# octosonarX2.net
KiCad netlist of a schematic drawn in EAGLE
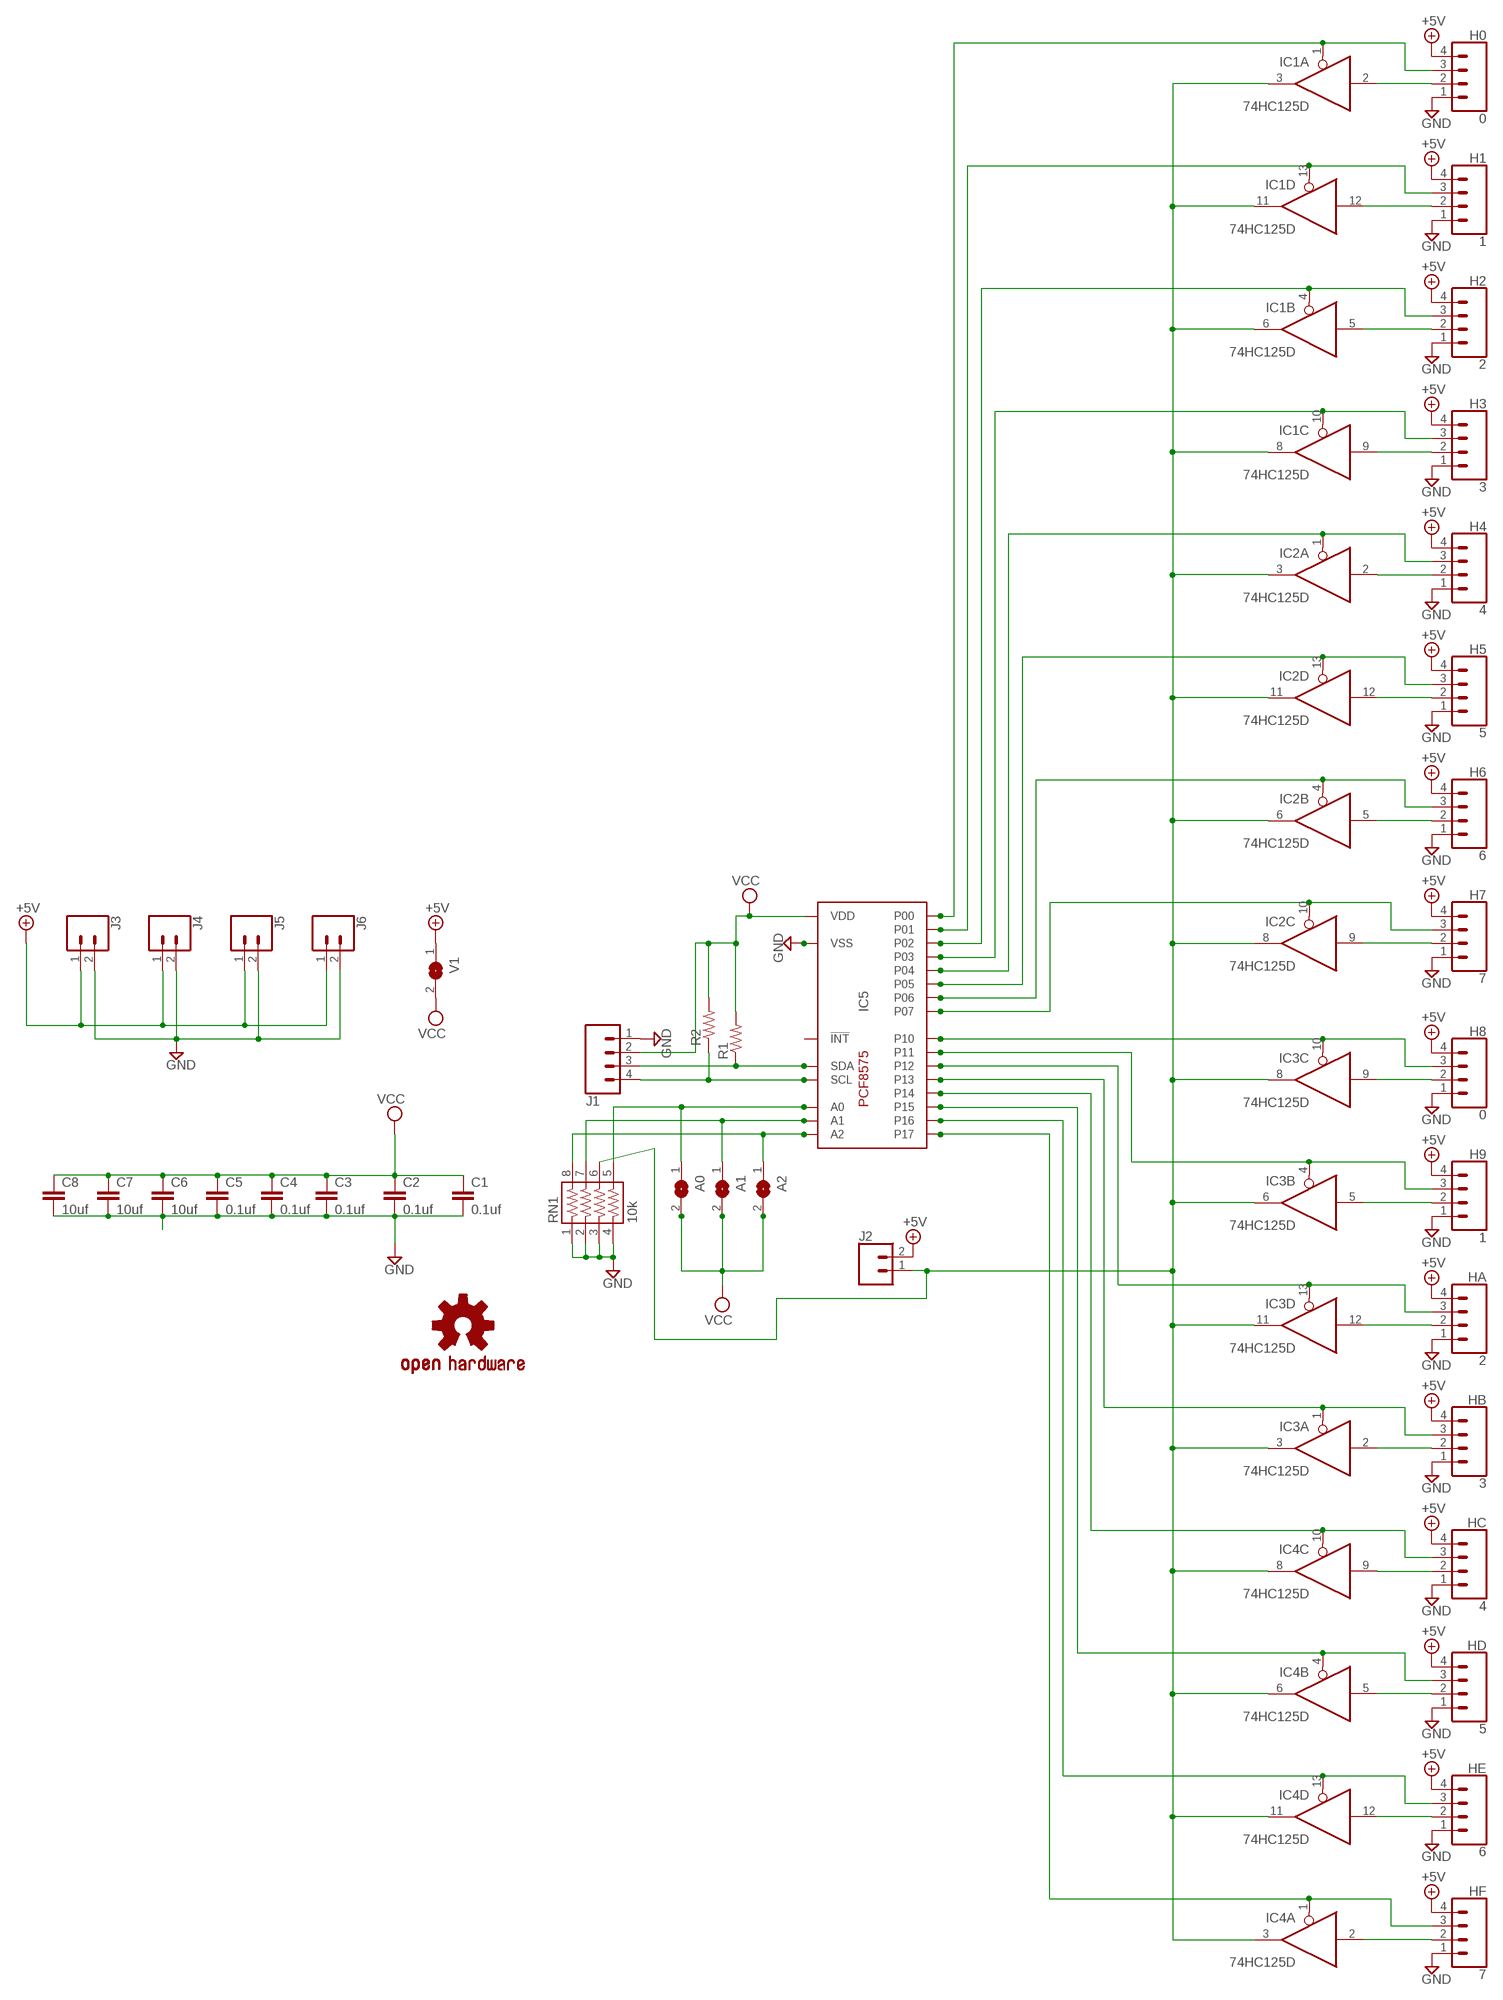
[diagram p0: schematic, sheet 1]

(export (version "E")
  (design (tool "Eeschema 10.0.6"))
  (components
    (comp (ref "A0") (value "SJ") (footprint "eagle-import:SJ") (libsource (lib "eagle-import") (part "SJ")))
    (comp (ref "A1") (value "SJ") (footprint "eagle-import:SJ") (libsource (lib "eagle-import") (part "SJ")))
    (comp (ref "A2") (value "SJ") (footprint "eagle-import:SJ") (libsource (lib "eagle-import") (part "SJ")))
    (comp (ref "C1")
      (value "0.1uf")
      (footprint "eagle-import:C0603")
      (libsource (lib "eagle-import") (part "C-EUC0603"))
    )
    (comp (ref "C2")
      (value "0.1uf")
      (footprint "eagle-import:C0603")
      (libsource (lib "eagle-import") (part "C-EUC0603"))
    )
    (comp (ref "C3")
      (value "0.1uf")
      (footprint "eagle-import:C0603")
      (libsource (lib "eagle-import") (part "C-EUC0603"))
    )
    (comp (ref "C4")
      (value "0.1uf")
      (footprint "eagle-import:C0603")
      (libsource (lib "eagle-import") (part "C-EUC0603"))
    )
    (comp (ref "C5")
      (value "0.1uf")
      (footprint "eagle-import:C0603")
      (libsource (lib "eagle-import") (part "C-EUC0603"))
    )
    (comp (ref "C6")
      (value "10uf")
      (footprint "eagle-import:C0603")
      (libsource (lib "eagle-import") (part "C-EUC0603"))
    )
    (comp (ref "C7")
      (value "10uf")
      (footprint "eagle-import:C0805")
      (libsource (lib "eagle-import") (part "C-EUC0805"))
    )
    (comp (ref "C8")
      (value "10uf")
      (footprint "eagle-import:C0805")
      (libsource (lib "eagle-import") (part "C-EUC0805"))
    )
    (comp (ref "H0")
      (value "0")
      (footprint "eagle-import:1X04")
      (libsource (lib "eagle-import") (part "CONN_04"))
    )
    (comp (ref "H1")
      (value "1")
      (footprint "eagle-import:1X04")
      (libsource (lib "eagle-import") (part "CONN_04"))
    )
    (comp (ref "H2")
      (value "2")
      (footprint "eagle-import:1X04")
      (libsource (lib "eagle-import") (part "CONN_04"))
    )
    (comp (ref "H3")
      (value "3")
      (footprint "eagle-import:1X04")
      (libsource (lib "eagle-import") (part "CONN_04"))
    )
    (comp (ref "H4")
      (value "4")
      (footprint "eagle-import:1X04")
      (libsource (lib "eagle-import") (part "CONN_04"))
    )
    (comp (ref "H5")
      (value "5")
      (footprint "eagle-import:1X04")
      (libsource (lib "eagle-import") (part "CONN_04"))
    )
    (comp (ref "H6")
      (value "6")
      (footprint "eagle-import:1X04")
      (libsource (lib "eagle-import") (part "CONN_04"))
    )
    (comp (ref "H7")
      (value "7")
      (footprint "eagle-import:1X04")
      (libsource (lib "eagle-import") (part "CONN_04"))
    )
    (comp (ref "H8")
      (value "0")
      (footprint "eagle-import:1X04")
      (libsource (lib "eagle-import") (part "CONN_04"))
    )
    (comp (ref "H9")
      (value "1")
      (footprint "eagle-import:1X04")
      (libsource (lib "eagle-import") (part "CONN_04"))
    )
    (comp (ref "HA")
      (value "2")
      (footprint "eagle-import:1X04")
      (libsource (lib "eagle-import") (part "CONN_04"))
    )
    (comp (ref "HB")
      (value "3")
      (footprint "eagle-import:1X04")
      (libsource (lib "eagle-import") (part "CONN_04"))
    )
    (comp (ref "HC")
      (value "4")
      (footprint "eagle-import:1X04")
      (libsource (lib "eagle-import") (part "CONN_04"))
    )
    (comp (ref "HD")
      (value "5")
      (footprint "eagle-import:1X04")
      (libsource (lib "eagle-import") (part "CONN_04"))
    )
    (comp (ref "HE")
      (value "6")
      (footprint "eagle-import:1X04")
      (libsource (lib "eagle-import") (part "CONN_04"))
    )
    (comp (ref "HF")
      (value "7")
      (footprint "eagle-import:1X04")
      (libsource (lib "eagle-import") (part "CONN_04"))
    )
    (comp (ref "IC1")
      (value "74HC125D")
      (footprint "eagle-import:SO14")
      (libsource (lib "eagle-import") (part "74125DHC"))
    )
    (comp (ref "IC2")
      (value "74HC125D")
      (footprint "eagle-import:SO14")
      (libsource (lib "eagle-import") (part "74125DHC"))
    )
    (comp (ref "IC3")
      (value "74HC125D")
      (footprint "eagle-import:SO14")
      (libsource (lib "eagle-import") (part "74xx-eu_85_74125DHC"))
    )
    (comp (ref "IC4")
      (value "74HC125D")
      (footprint "eagle-import:SO14")
      (libsource (lib "eagle-import") (part "74xx-eu_85_74125DHC"))
    )
    (comp (ref "IC5")
      (value "PCF8575C")
      (footprint "eagle-import:SOP24")
      (libsource (lib "eagle-import") (part "PCF8575C"))
    )
    (comp (ref "J1")
      (value "CONN_04POLAR_LOCK")
      (footprint "eagle-import:MOLEX-1X4_LOCK")
      (libsource (lib "eagle-import") (part "CONN_04POLAR_LOCK"))
    )
    (comp (ref "J2")
      (value "CONN_02POLAR_LOCK")
      (footprint "eagle-import:MOLEX-1X2_LOCK")
      (libsource (lib "eagle-import") (part "CONN_02POLAR_LOCK"))
    )
    (comp (ref "J3")
      (value "CONN_02")
      (footprint "eagle-import:1X02")
      (libsource (lib "eagle-import") (part "CONN_02"))
    )
    (comp (ref "J4")
      (value "CONN_02")
      (footprint "eagle-import:1X02")
      (libsource (lib "eagle-import") (part "CONN_02"))
    )
    (comp (ref "J5")
      (value "CONN_02")
      (footprint "eagle-import:1X02")
      (libsource (lib "eagle-import") (part "CONN_02"))
    )
    (comp (ref "J6")
      (value "CONN_02")
      (footprint "eagle-import:1X02")
      (libsource (lib "eagle-import") (part "CONN_02"))
    )
    (comp (ref "LOGO1")
      (value "OSHW-LOGOL")
      (footprint "eagle-import:OSHW-LOGO-L")
      (libsource (lib "eagle-import") (part "OSHW-LOGOL"))
    )
    (comp (ref "R1")
      (value "R-US_0204/2V")
      (footprint "eagle-import:0204V")
      (libsource (lib "eagle-import") (part "R-US_0204/2V"))
    )
    (comp (ref "R2")
      (value "R-US_0204/2V")
      (footprint "eagle-import:0204V")
      (libsource (lib "eagle-import") (part "R-US_0204/2V"))
    )
    (comp (ref "RN1")
      (value "10k")
      (footprint "eagle-import:743-8")
      (libsource (lib "eagle-import") (part "743-8"))
    )
    (comp (ref "V1") (value "SJ") (footprint "eagle-import:SJ") (libsource (lib "eagle-import") (part "SJ")))
  )
  (nets
    (net (code "1") (name "+5V") (class "Default")
      (node (ref "H0") (pin "4") (pinfunction "4_4") (pintype "passive"))
      (node (ref "H1") (pin "4") (pinfunction "4_4") (pintype "passive"))
      (node (ref "H2") (pin "4") (pinfunction "4_4") (pintype "passive"))
      (node (ref "H3") (pin "4") (pinfunction "4_4") (pintype "passive"))
      (node (ref "H4") (pin "4") (pinfunction "4_4") (pintype "passive"))
      (node (ref "H5") (pin "4") (pinfunction "4_4") (pintype "passive"))
      (node (ref "H6") (pin "4") (pinfunction "4_4") (pintype "passive"))
      (node (ref "H7") (pin "4") (pinfunction "4_4") (pintype "passive"))
      (node (ref "H8") (pin "4") (pinfunction "4_4") (pintype "passive"))
      (node (ref "H9") (pin "4") (pinfunction "4_4") (pintype "passive"))
      (node (ref "HA") (pin "4") (pinfunction "4_4") (pintype "passive"))
      (node (ref "HB") (pin "4") (pinfunction "4_4") (pintype "passive"))
      (node (ref "HC") (pin "4") (pinfunction "4_4") (pintype "passive"))
      (node (ref "HD") (pin "4") (pinfunction "4_4") (pintype "passive"))
      (node (ref "HE") (pin "4") (pinfunction "4_4") (pintype "passive"))
      (node (ref "HF") (pin "4") (pinfunction "4_4") (pintype "passive"))
      (node (ref "J2") (pin "2") (pinfunction "2_2") (pintype "passive"))
      (node (ref "J3") (pin "1") (pinfunction "1_1") (pintype "passive"))
      (node (ref "J4") (pin "1") (pinfunction "1_1") (pintype "passive"))
      (node (ref "J5") (pin "1") (pinfunction "1_1") (pintype "passive"))
      (node (ref "J6") (pin "1") (pinfunction "1_1") (pintype "passive"))
      (node (ref "V1") (pin "1") (pinfunction "1_1") (pintype "passive"))
    )
    (net (code "2") (name "GND") (class "Default")
      (node (ref "C1") (pin "2") (pinfunction "2_2") (pintype "passive"))
      (node (ref "C2") (pin "2") (pinfunction "2_2") (pintype "passive"))
      (node (ref "C3") (pin "2") (pinfunction "2_2") (pintype "passive"))
      (node (ref "C4") (pin "2") (pinfunction "2_2") (pintype "passive"))
      (node (ref "C5") (pin "2") (pinfunction "2_2") (pintype "passive"))
      (node (ref "C6") (pin "2") (pinfunction "2_2") (pintype "passive"))
      (node (ref "C7") (pin "2") (pinfunction "2_2") (pintype "passive"))
      (node (ref "C8") (pin "2") (pinfunction "2_2") (pintype "passive"))
      (node (ref "H0") (pin "1") (pinfunction "1_1") (pintype "passive"))
      (node (ref "H1") (pin "1") (pinfunction "1_1") (pintype "passive"))
      (node (ref "H2") (pin "1") (pinfunction "1_1") (pintype "passive"))
      (node (ref "H3") (pin "1") (pinfunction "1_1") (pintype "passive"))
      (node (ref "H4") (pin "1") (pinfunction "1_1") (pintype "passive"))
      (node (ref "H5") (pin "1") (pinfunction "1_1") (pintype "passive"))
      (node (ref "H6") (pin "1") (pinfunction "1_1") (pintype "passive"))
      (node (ref "H7") (pin "1") (pinfunction "1_1") (pintype "passive"))
      (node (ref "H8") (pin "1") (pinfunction "1_1") (pintype "passive"))
      (node (ref "H9") (pin "1") (pinfunction "1_1") (pintype "passive"))
      (node (ref "HA") (pin "1") (pinfunction "1_1") (pintype "passive"))
      (node (ref "HB") (pin "1") (pinfunction "1_1") (pintype "passive"))
      (node (ref "HC") (pin "1") (pinfunction "1_1") (pintype "passive"))
      (node (ref "HD") (pin "1") (pinfunction "1_1") (pintype "passive"))
      (node (ref "HE") (pin "1") (pinfunction "1_1") (pintype "passive"))
      (node (ref "HF") (pin "1") (pinfunction "1_1") (pintype "passive"))
      (node (ref "IC5") (pin "P$12") (pinfunction "VSS_P$12") (pintype "power_in"))
      (node (ref "J1") (pin "1") (pinfunction "1_1") (pintype "passive"))
      (node (ref "J3") (pin "2") (pinfunction "2_2") (pintype "passive"))
      (node (ref "J4") (pin "2") (pinfunction "2_2") (pintype "passive"))
      (node (ref "J5") (pin "2") (pinfunction "2_2") (pintype "passive"))
      (node (ref "J6") (pin "2") (pinfunction "2_2") (pintype "passive"))
      (node (ref "RN1") (pin "1") (pinfunction "1_1") (pintype "passive"))
      (node (ref "RN1") (pin "2") (pinfunction "2_2") (pintype "passive"))
      (node (ref "RN1") (pin "3") (pinfunction "3_3") (pintype "passive"))
      (node (ref "RN1") (pin "4") (pinfunction "4_4") (pintype "passive"))
    )
    (net (code "3") (name "Net-(IC1A-I)") (class "Default")
      (node (ref "H0") (pin "2") (pinfunction "2_2") (pintype "passive"))
      (node (ref "IC1") (pin "2") (pinfunction "I_2") (pintype "input"))
    )
    (net (code "4") (name "Net-(IC1A-O)") (class "Default")
      (node (ref "IC1") (pin "11") (pinfunction "O_11") (pintype "tri_state"))
      (node (ref "IC1") (pin "3") (pinfunction "O_3") (pintype "tri_state"))
      (node (ref "IC1") (pin "6") (pinfunction "O_6") (pintype "tri_state"))
      (node (ref "IC1") (pin "8") (pinfunction "O_8") (pintype "tri_state"))
      (node (ref "IC2") (pin "11") (pinfunction "O_11") (pintype "tri_state"))
      (node (ref "IC2") (pin "3") (pinfunction "O_3") (pintype "tri_state"))
      (node (ref "IC2") (pin "6") (pinfunction "O_6") (pintype "tri_state"))
      (node (ref "IC2") (pin "8") (pinfunction "O_8") (pintype "tri_state"))
      (node (ref "IC3") (pin "11") (pinfunction "O_11") (pintype "tri_state"))
      (node (ref "IC3") (pin "3") (pinfunction "O_3") (pintype "tri_state"))
      (node (ref "IC3") (pin "6") (pinfunction "O_6") (pintype "tri_state"))
      (node (ref "IC3") (pin "8") (pinfunction "O_8") (pintype "tri_state"))
      (node (ref "IC4") (pin "11") (pinfunction "O_11") (pintype "tri_state"))
      (node (ref "IC4") (pin "3") (pinfunction "O_3") (pintype "tri_state"))
      (node (ref "IC4") (pin "6") (pinfunction "O_6") (pintype "tri_state"))
      (node (ref "IC4") (pin "8") (pinfunction "O_8") (pintype "tri_state"))
      (node (ref "J2") (pin "1") (pinfunction "1_1") (pintype "passive"))
      (node (ref "RN1") (pin "6") (pinfunction "6_6") (pintype "passive"))
    )
    (net (code "5") (name "Net-(IC1A-OE)") (class "Default")
      (node (ref "H0") (pin "3") (pinfunction "3_3") (pintype "passive"))
      (node (ref "IC1") (pin "1") (pinfunction "OE_1") (pintype "input"))
      (node (ref "IC5") (pin "P$4") (pinfunction "P00_P$4") (pintype "bidirectional"))
    )
    (net (code "6") (name "Net-(IC1B-I)") (class "Default")
      (node (ref "H2") (pin "2") (pinfunction "2_2") (pintype "passive"))
      (node (ref "IC1") (pin "5") (pinfunction "I_5") (pintype "input"))
    )
    (net (code "7") (name "Net-(IC1B-OE)") (class "Default")
      (node (ref "H2") (pin "3") (pinfunction "3_3") (pintype "passive"))
      (node (ref "IC1") (pin "4") (pinfunction "OE_4") (pintype "input"))
      (node (ref "IC5") (pin "P$6") (pinfunction "P02_P$6") (pintype "bidirectional"))
    )
    (net (code "8") (name "Net-(IC1C-I)") (class "Default")
      (node (ref "H3") (pin "2") (pinfunction "2_2") (pintype "passive"))
      (node (ref "IC1") (pin "9") (pinfunction "I_9") (pintype "input"))
    )
    (net (code "9") (name "Net-(IC1C-OE)") (class "Default")
      (node (ref "H3") (pin "3") (pinfunction "3_3") (pintype "passive"))
      (node (ref "IC1") (pin "10") (pinfunction "OE_10") (pintype "input"))
      (node (ref "IC5") (pin "P$7") (pinfunction "P03_P$7") (pintype "bidirectional"))
    )
    (net (code "10") (name "Net-(IC1D-I)") (class "Default")
      (node (ref "H1") (pin "2") (pinfunction "2_2") (pintype "passive"))
      (node (ref "IC1") (pin "12") (pinfunction "I_12") (pintype "input"))
    )
    (net (code "11") (name "Net-(IC1D-OE)") (class "Default")
      (node (ref "H1") (pin "3") (pinfunction "3_3") (pintype "passive"))
      (node (ref "IC1") (pin "13") (pinfunction "OE_13") (pintype "input"))
      (node (ref "IC5") (pin "P$5") (pinfunction "P01_P$5") (pintype "bidirectional"))
    )
    (net (code "12") (name "Net-(IC2A-I)") (class "Default")
      (node (ref "H4") (pin "2") (pinfunction "2_2") (pintype "passive"))
      (node (ref "IC2") (pin "2") (pinfunction "I_2") (pintype "input"))
    )
    (net (code "13") (name "Net-(IC2A-OE)") (class "Default")
      (node (ref "H4") (pin "3") (pinfunction "3_3") (pintype "passive"))
      (node (ref "IC2") (pin "1") (pinfunction "OE_1") (pintype "input"))
      (node (ref "IC5") (pin "P$8") (pinfunction "P04_P$8") (pintype "bidirectional"))
    )
    (net (code "14") (name "Net-(IC2B-I)") (class "Default")
      (node (ref "H6") (pin "2") (pinfunction "2_2") (pintype "passive"))
      (node (ref "IC2") (pin "5") (pinfunction "I_5") (pintype "input"))
    )
    (net (code "15") (name "Net-(IC2B-OE)") (class "Default")
      (node (ref "H6") (pin "3") (pinfunction "3_3") (pintype "passive"))
      (node (ref "IC2") (pin "4") (pinfunction "OE_4") (pintype "input"))
      (node (ref "IC5") (pin "P$10") (pinfunction "P06_P$10") (pintype "bidirectional"))
    )
    (net (code "16") (name "Net-(IC2C-I)") (class "Default")
      (node (ref "H7") (pin "2") (pinfunction "2_2") (pintype "passive"))
      (node (ref "IC2") (pin "9") (pinfunction "I_9") (pintype "input"))
    )
    (net (code "17") (name "Net-(IC2C-OE)") (class "Default")
      (node (ref "H7") (pin "3") (pinfunction "3_3") (pintype "passive"))
      (node (ref "IC2") (pin "10") (pinfunction "OE_10") (pintype "input"))
      (node (ref "IC5") (pin "P$11") (pinfunction "P07_P$11") (pintype "bidirectional"))
    )
    (net (code "18") (name "Net-(IC2D-I)") (class "Default")
      (node (ref "H5") (pin "2") (pinfunction "2_2") (pintype "passive"))
      (node (ref "IC2") (pin "12") (pinfunction "I_12") (pintype "input"))
    )
    (net (code "19") (name "Net-(IC2D-OE)") (class "Default")
      (node (ref "H5") (pin "3") (pinfunction "3_3") (pintype "passive"))
      (node (ref "IC2") (pin "13") (pinfunction "OE_13") (pintype "input"))
      (node (ref "IC5") (pin "P$9") (pinfunction "P05_P$9") (pintype "bidirectional"))
    )
    (net (code "20") (name "Net-(IC3A-I)") (class "Default")
      (node (ref "HB") (pin "2") (pinfunction "2_2") (pintype "passive"))
      (node (ref "IC3") (pin "2") (pinfunction "I_2") (pintype "input"))
    )
    (net (code "21") (name "Net-(IC3A-OE)") (class "Default")
      (node (ref "HB") (pin "3") (pinfunction "3_3") (pintype "passive"))
      (node (ref "IC3") (pin "1") (pinfunction "OE_1") (pintype "input"))
      (node (ref "IC5") (pin "P$16") (pinfunction "P13_P$16") (pintype "bidirectional"))
    )
    (net (code "22") (name "Net-(IC3B-I)") (class "Default")
      (node (ref "H9") (pin "2") (pinfunction "2_2") (pintype "passive"))
      (node (ref "IC3") (pin "5") (pinfunction "I_5") (pintype "input"))
    )
    (net (code "23") (name "Net-(IC3B-OE)") (class "Default")
      (node (ref "H9") (pin "3") (pinfunction "3_3") (pintype "passive"))
      (node (ref "IC3") (pin "4") (pinfunction "OE_4") (pintype "input"))
      (node (ref "IC5") (pin "P$14") (pinfunction "P11_P$14") (pintype "bidirectional"))
    )
    (net (code "24") (name "Net-(IC3C-I)") (class "Default")
      (node (ref "H8") (pin "2") (pinfunction "2_2") (pintype "passive"))
      (node (ref "IC3") (pin "9") (pinfunction "I_9") (pintype "input"))
    )
    (net (code "25") (name "Net-(IC3C-OE)") (class "Default")
      (node (ref "H8") (pin "3") (pinfunction "3_3") (pintype "passive"))
      (node (ref "IC3") (pin "10") (pinfunction "OE_10") (pintype "input"))
      (node (ref "IC5") (pin "P$13") (pinfunction "P10_P$13") (pintype "bidirectional"))
    )
    (net (code "26") (name "Net-(IC3D-I)") (class "Default")
      (node (ref "HA") (pin "2") (pinfunction "2_2") (pintype "passive"))
      (node (ref "IC3") (pin "12") (pinfunction "I_12") (pintype "input"))
    )
    (net (code "27") (name "Net-(IC3D-OE)") (class "Default")
      (node (ref "HA") (pin "3") (pinfunction "3_3") (pintype "passive"))
      (node (ref "IC3") (pin "13") (pinfunction "OE_13") (pintype "input"))
      (node (ref "IC5") (pin "P$15") (pinfunction "P12_P$15") (pintype "bidirectional"))
    )
    (net (code "28") (name "Net-(IC4A-I)") (class "Default")
      (node (ref "HF") (pin "2") (pinfunction "2_2") (pintype "passive"))
      (node (ref "IC4") (pin "2") (pinfunction "I_2") (pintype "input"))
    )
    (net (code "29") (name "Net-(IC4A-OE)") (class "Default")
      (node (ref "HF") (pin "3") (pinfunction "3_3") (pintype "passive"))
      (node (ref "IC4") (pin "1") (pinfunction "OE_1") (pintype "input"))
      (node (ref "IC5") (pin "P$20") (pinfunction "P17_P$20") (pintype "bidirectional"))
    )
    (net (code "30") (name "Net-(IC4B-I)") (class "Default")
      (node (ref "HD") (pin "2") (pinfunction "2_2") (pintype "passive"))
      (node (ref "IC4") (pin "5") (pinfunction "I_5") (pintype "input"))
    )
    (net (code "31") (name "Net-(IC4B-OE)") (class "Default")
      (node (ref "HD") (pin "3") (pinfunction "3_3") (pintype "passive"))
      (node (ref "IC4") (pin "4") (pinfunction "OE_4") (pintype "input"))
      (node (ref "IC5") (pin "P$18") (pinfunction "P15_P$18") (pintype "bidirectional"))
    )
    (net (code "32") (name "Net-(IC4C-I)") (class "Default")
      (node (ref "HC") (pin "2") (pinfunction "2_2") (pintype "passive"))
      (node (ref "IC4") (pin "9") (pinfunction "I_9") (pintype "input"))
    )
    (net (code "33") (name "Net-(IC4C-OE)") (class "Default")
      (node (ref "HC") (pin "3") (pinfunction "3_3") (pintype "passive"))
      (node (ref "IC4") (pin "10") (pinfunction "OE_10") (pintype "input"))
      (node (ref "IC5") (pin "P$17") (pinfunction "P14_P$17") (pintype "bidirectional"))
    )
    (net (code "34") (name "Net-(IC4D-I)") (class "Default")
      (node (ref "HE") (pin "2") (pinfunction "2_2") (pintype "passive"))
      (node (ref "IC4") (pin "12") (pinfunction "I_12") (pintype "input"))
    )
    (net (code "35") (name "Net-(IC4D-OE)") (class "Default")
      (node (ref "HE") (pin "3") (pinfunction "3_3") (pintype "passive"))
      (node (ref "IC4") (pin "13") (pinfunction "OE_13") (pintype "input"))
      (node (ref "IC5") (pin "P$19") (pinfunction "P16_P$19") (pintype "bidirectional"))
    )
    (net (code "36") (name "Net-(IC5-A0)") (class "Default")
      (node (ref "A0") (pin "1") (pinfunction "1_1") (pintype "passive"))
      (node (ref "IC5") (pin "P$21") (pinfunction "A0_P$21") (pintype "input"))
      (node (ref "RN1") (pin "5") (pinfunction "5_5") (pintype "passive"))
    )
    (net (code "37") (name "Net-(IC5-A1)") (class "Default")
      (node (ref "A1") (pin "1") (pinfunction "1_1") (pintype "passive"))
      (node (ref "IC5") (pin "P$2") (pinfunction "A1_P$2") (pintype "input"))
      (node (ref "RN1") (pin "7") (pinfunction "7_7") (pintype "passive"))
    )
    (net (code "38") (name "Net-(IC5-A2)") (class "Default")
      (node (ref "A2") (pin "1") (pinfunction "1_1") (pintype "passive"))
      (node (ref "IC5") (pin "P$3") (pinfunction "A2_P$3") (pintype "input"))
      (node (ref "RN1") (pin "8") (pinfunction "8_8") (pintype "passive"))
    )
    (net (code "39") (name "Net-(IC5-SCL)") (class "Default")
      (node (ref "IC5") (pin "P$22") (pinfunction "SCL_P$22") (pintype "input"))
      (node (ref "J1") (pin "4") (pinfunction "4_4") (pintype "passive"))
      (node (ref "R2") (pin "1") (pinfunction "1_1") (pintype "passive"))
    )
    (net (code "40") (name "Net-(IC5-SDA)") (class "Default")
      (node (ref "IC5") (pin "P$23") (pinfunction "SDA_P$23") (pintype "bidirectional"))
      (node (ref "J1") (pin "3") (pinfunction "3_3") (pintype "passive"))
      (node (ref "R1") (pin "1") (pinfunction "1_1") (pintype "passive"))
    )
    (net (code "41") (name "VCC") (class "Default")
      (node (ref "A0") (pin "2") (pinfunction "2_2") (pintype "passive"))
      (node (ref "A1") (pin "2") (pinfunction "2_2") (pintype "passive"))
      (node (ref "A2") (pin "2") (pinfunction "2_2") (pintype "passive"))
      (node (ref "C1") (pin "1") (pinfunction "1_1") (pintype "passive"))
      (node (ref "C2") (pin "1") (pinfunction "1_1") (pintype "passive"))
      (node (ref "C3") (pin "1") (pinfunction "1_1") (pintype "passive"))
      (node (ref "C4") (pin "1") (pinfunction "1_1") (pintype "passive"))
      (node (ref "C5") (pin "1") (pinfunction "1_1") (pintype "passive"))
      (node (ref "C6") (pin "1") (pinfunction "1_1") (pintype "passive"))
      (node (ref "C7") (pin "1") (pinfunction "1_1") (pintype "passive"))
      (node (ref "C8") (pin "1") (pinfunction "1_1") (pintype "passive"))
      (node (ref "IC5") (pin "P$24") (pinfunction "VDD_P$24") (pintype "power_in"))
      (node (ref "J1") (pin "2") (pinfunction "2_2") (pintype "passive"))
      (node (ref "R1") (pin "2") (pinfunction "2_2") (pintype "passive"))
      (node (ref "R2") (pin "2") (pinfunction "2_2") (pintype "passive"))
      (node (ref "V1") (pin "2") (pinfunction "2_2") (pintype "passive"))
    )
    (net (code "42") (name "unconnected-(IC5-~{INT}-PadP$1)") (class "Default")
      (node (ref "IC5") (pin "P$1") (pinfunction "~{INT}_P$1") (pintype "open_collector"))
    )
  )
)
